# at90usb.net
KiCad netlist of a schematic drawn in EAGLE
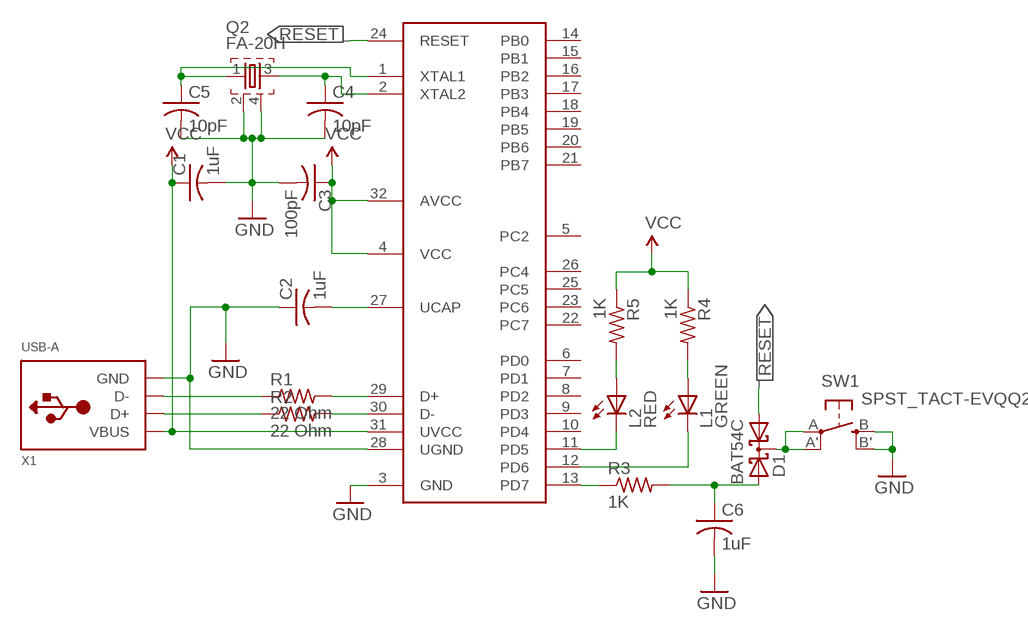
[diagram p0: schematic, sheet 1]

(export (version "E")
  (design (tool "Eeschema 10.0.6"))
  (components
    (comp (ref "C1")
      (value "1uF")
      (footprint "eagle-import:C0805K")
      (fields (field (name "MPN") "06033D105MAT2A"))
      (libsource (lib "eagle-import") (part "C-USC0805K"))
    )
    (comp (ref "C2")
      (value "1uF")
      (footprint "eagle-import:C0805K")
      (fields (field (name "MPN") "06033D105MAT2A"))
      (libsource (lib "eagle-import") (part "C-USC0805K"))
    )
    (comp (ref "C3")
      (value "100pF")
      (footprint "eagle-import:C0805K")
      (fields (field (name "MPN") "0603YC104K4Z2A"))
      (libsource (lib "eagle-import") (part "C-USC0805K"))
    )
    (comp (ref "C4")
      (value "10pF")
      (footprint "eagle-import:C0805")
      (libsource (lib "eagle-import") (part "C-USC0805"))
    )
    (comp (ref "C5")
      (value "10pF")
      (footprint "eagle-import:C0805")
      (libsource (lib "eagle-import") (part "C-USC0805"))
    )
    (comp (ref "C6")
      (value "1uF")
      (footprint "eagle-import:C0805K")
      (fields (field (name "MPN") "06033D105MAT2A"))
      (libsource (lib "eagle-import") (part "C-USC0805K"))
    )
    (comp (ref "D1")
      (value "BAT54C")
      (footprint "eagle-import:SOT23")
      (libsource (lib "eagle-import") (part "BAT54C"))
    )
    (comp (ref "L1")
      (value "GREEN")
      (footprint "eagle-import:CHIPLED_1206")
      (libsource (lib "eagle-import") (part "LEDCHIPLED_1206"))
    )
    (comp (ref "L2")
      (value "RED")
      (footprint "eagle-import:CHIPLED_1206")
      (libsource (lib "eagle-import") (part "LEDCHIPLED_1206"))
    )
    (comp (ref "Q2")
      (value "FA-20H")
      (footprint "eagle-import:FA-20H")
      (libsource (lib "eagle-import") (part "FA-20H"))
    )
    (comp (ref "R1")
      (value "22 Ohm")
      (footprint "eagle-import:M0805")
      (libsource (lib "eagle-import") (part "R-US_M0805"))
    )
    (comp (ref "R2")
      (value "22 Ohm")
      (footprint "eagle-import:M0805")
      (libsource (lib "eagle-import") (part "R-US_M0805"))
    )
    (comp (ref "R3")
      (value "1K")
      (footprint "eagle-import:M0805")
      (libsource (lib "eagle-import") (part "R-US_M0805"))
    )
    (comp (ref "R4")
      (value "1K")
      (footprint "eagle-import:M0805")
      (libsource (lib "eagle-import") (part "R-US_M0805"))
    )
    (comp (ref "R5")
      (value "1K")
      (footprint "eagle-import:M0805")
      (libsource (lib "eagle-import") (part "R-US_M0805"))
    )
    (comp (ref "SW1")
      (value "SPST_TACT-EVQQ2")
      (footprint "eagle-import:EVQ-Q2")
      (libsource (lib "eagle-import") (part "SPST_TACT-EVQQ2"))
    )
    (comp (ref "U1")
      (value "AT90USB162")
      (footprint "eagle-import:VQFP32")
      (libsource (lib "eagle-import") (part "AT90USB162"))
    )
    (comp (ref "X1")
      (value "USB-A")
      (footprint "eagle-import:MOLEX_480371000")
      (libsource (lib "eagle-import") (part "USB-A"))
    )
  )
  (nets
    (net (code "1") (name "/RESET") (class "Default")
      (node (ref "D1") (pin "1") (pinfunction "A1_1") (pintype "passive"))
      (node (ref "U1") (pin "24") (pinfunction "RESET_24") (pintype "bidirectional"))
    )
    (net (code "2") (name "GND") (class "Default")
      (node (ref "C1") (pin "2") (pinfunction "2_2") (pintype "passive"))
      (node (ref "C2") (pin "1") (pinfunction "1_1") (pintype "passive"))
      (node (ref "C3") (pin "2") (pinfunction "2_2") (pintype "passive"))
      (node (ref "C4") (pin "2") (pinfunction "2_2") (pintype "passive"))
      (node (ref "C5") (pin "2") (pinfunction "2_2") (pintype "passive"))
      (node (ref "C6") (pin "2") (pinfunction "2_2") (pintype "passive"))
      (node (ref "Q2") (pin "2") (pinfunction "2_2") (pintype "passive"))
      (node (ref "Q2") (pin "4") (pinfunction "4_4") (pintype "passive"))
      (node (ref "SW1") (pin "B") (pinfunction "S_B") (pintype "passive"))
      (node (ref "SW1") (pin "B'") (pinfunction "S1_B'") (pintype "passive"))
      (node (ref "U1") (pin "28") (pinfunction "UGND_28") (pintype "bidirectional"))
      (node (ref "U1") (pin "3") (pinfunction "GND_3") (pintype "power_in"))
      (node (ref "X1") (pin "4") (pinfunction "GND_4") (pintype "power_in"))
    )
    (net (code "3") (name "Net-(D1-A2)") (class "Default")
      (node (ref "C6") (pin "1") (pinfunction "1_1") (pintype "passive"))
      (node (ref "D1") (pin "2") (pinfunction "A2_2") (pintype "passive"))
      (node (ref "R3") (pin "2") (pinfunction "2_2") (pintype "passive"))
    )
    (net (code "4") (name "Net-(D1-CC)") (class "Default")
      (node (ref "D1") (pin "3") (pinfunction "CC_3") (pintype "passive"))
      (node (ref "SW1") (pin "A") (pinfunction "P_A") (pintype "passive"))
      (node (ref "SW1") (pin "A'") (pinfunction "P1_A'") (pintype "passive"))
    )
    (net (code "5") (name "Net-(L1-PadA)") (class "Default")
      (node (ref "L1") (pin "A") (pinfunction "A_A") (pintype "passive"))
      (node (ref "R4") (pin "2") (pinfunction "2_2") (pintype "passive"))
    )
    (net (code "6") (name "Net-(L2-PadA)") (class "Default")
      (node (ref "L2") (pin "A") (pinfunction "A_A") (pintype "passive"))
      (node (ref "R5") (pin "2") (pinfunction "2_2") (pintype "passive"))
    )
    (net (code "7") (name "Net-(U1-D+)") (class "Default")
      (node (ref "R1") (pin "2") (pinfunction "2_2") (pintype "passive"))
      (node (ref "U1") (pin "29") (pinfunction "D+_29") (pintype "bidirectional"))
    )
    (net (code "8") (name "Net-(U1-D-)") (class "Default")
      (node (ref "R2") (pin "2") (pinfunction "2_2") (pintype "passive"))
      (node (ref "U1") (pin "30") (pinfunction "D-_30") (pintype "bidirectional"))
    )
    (net (code "9") (name "Net-(U1-PD5)") (class "Default")
      (node (ref "L2") (pin "C") (pinfunction "C_C") (pintype "passive"))
      (node (ref "U1") (pin "11") (pinfunction "PD5_11") (pintype "bidirectional"))
    )
    (net (code "10") (name "Net-(U1-PD6)") (class "Default")
      (node (ref "L1") (pin "C") (pinfunction "C_C") (pintype "passive"))
      (node (ref "U1") (pin "12") (pinfunction "PD6_12") (pintype "bidirectional"))
    )
    (net (code "11") (name "Net-(U1-PD7)") (class "Default")
      (node (ref "R3") (pin "1") (pinfunction "1_1") (pintype "passive"))
      (node (ref "U1") (pin "13") (pinfunction "PD7_13") (pintype "bidirectional"))
    )
    (net (code "12") (name "Net-(U1-UCAP)") (class "Default")
      (node (ref "C2") (pin "2") (pinfunction "2_2") (pintype "passive"))
      (node (ref "U1") (pin "27") (pinfunction "UCAP_27") (pintype "bidirectional"))
    )
    (net (code "13") (name "Net-(U1-XTAL1)") (class "Default")
      (node (ref "C5") (pin "1") (pinfunction "1_1") (pintype "passive"))
      (node (ref "Q2") (pin "1") (pinfunction "1_1") (pintype "passive"))
      (node (ref "U1") (pin "1") (pinfunction "XTAL1_1") (pintype "bidirectional"))
    )
    (net (code "14") (name "Net-(U1-XTAL2)") (class "Default")
      (node (ref "C4") (pin "1") (pinfunction "1_1") (pintype "passive"))
      (node (ref "Q2") (pin "3") (pinfunction "3_3") (pintype "passive"))
      (node (ref "U1") (pin "2") (pinfunction "XTAL2_2") (pintype "bidirectional"))
    )
    (net (code "15") (name "Net-(X1-D+)") (class "Default")
      (node (ref "R2") (pin "1") (pinfunction "1_1") (pintype "passive"))
      (node (ref "X1") (pin "3") (pinfunction "D+_3") (pintype "bidirectional"))
    )
    (net (code "16") (name "Net-(X1-D-)") (class "Default")
      (node (ref "R1") (pin "1") (pinfunction "1_1") (pintype "passive"))
      (node (ref "X1") (pin "2") (pinfunction "D-_2") (pintype "bidirectional"))
    )
    (net (code "17") (name "VCC") (class "Default")
      (node (ref "C1") (pin "1") (pinfunction "1_1") (pintype "passive"))
      (node (ref "C3") (pin "1") (pinfunction "1_1") (pintype "passive"))
      (node (ref "R4") (pin "1") (pinfunction "1_1") (pintype "passive"))
      (node (ref "R5") (pin "1") (pinfunction "1_1") (pintype "passive"))
      (node (ref "U1") (pin "31") (pinfunction "UVCC_31") (pintype "bidirectional"))
      (node (ref "U1") (pin "32") (pinfunction "AVCC_32") (pintype "bidirectional"))
      (node (ref "U1") (pin "4") (pinfunction "VCC_4") (pintype "power_in"))
      (node (ref "X1") (pin "1") (pinfunction "VBUS_1") (pintype "power_in"))
    )
    (net (code "18") (name "unconnected-(U1-PB0-Pad14)") (class "Default")
      (node (ref "U1") (pin "14") (pinfunction "PB0_14") (pintype "bidirectional"))
    )
    (net (code "19") (name "unconnected-(U1-PB1-Pad15)") (class "Default")
      (node (ref "U1") (pin "15") (pinfunction "PB1_15") (pintype "bidirectional"))
    )
    (net (code "20") (name "unconnected-(U1-PB2-Pad16)") (class "Default")
      (node (ref "U1") (pin "16") (pinfunction "PB2_16") (pintype "bidirectional"))
    )
    (net (code "21") (name "unconnected-(U1-PB3-Pad17)") (class "Default")
      (node (ref "U1") (pin "17") (pinfunction "PB3_17") (pintype "bidirectional"))
    )
    (net (code "22") (name "unconnected-(U1-PB4-Pad18)") (class "Default")
      (node (ref "U1") (pin "18") (pinfunction "PB4_18") (pintype "bidirectional"))
    )
    (net (code "23") (name "unconnected-(U1-PB5-Pad19)") (class "Default")
      (node (ref "U1") (pin "19") (pinfunction "PB5_19") (pintype "bidirectional"))
    )
    (net (code "24") (name "unconnected-(U1-PB6-Pad20)") (class "Default")
      (node (ref "U1") (pin "20") (pinfunction "PB6_20") (pintype "bidirectional"))
    )
    (net (code "25") (name "unconnected-(U1-PB7-Pad21)") (class "Default")
      (node (ref "U1") (pin "21") (pinfunction "PB7_21") (pintype "bidirectional"))
    )
    (net (code "26") (name "unconnected-(U1-PC2-Pad5)") (class "Default")
      (node (ref "U1") (pin "5") (pinfunction "PC2_5") (pintype "bidirectional"))
    )
    (net (code "27") (name "unconnected-(U1-PC4-Pad26)") (class "Default")
      (node (ref "U1") (pin "26") (pinfunction "PC4_26") (pintype "bidirectional"))
    )
    (net (code "28") (name "unconnected-(U1-PC5-Pad25)") (class "Default")
      (node (ref "U1") (pin "25") (pinfunction "PC5_25") (pintype "bidirectional"))
    )
    (net (code "29") (name "unconnected-(U1-PC6-Pad23)") (class "Default")
      (node (ref "U1") (pin "23") (pinfunction "PC6_23") (pintype "bidirectional"))
    )
    (net (code "30") (name "unconnected-(U1-PC7-Pad22)") (class "Default")
      (node (ref "U1") (pin "22") (pinfunction "PC7_22") (pintype "bidirectional"))
    )
    (net (code "31") (name "unconnected-(U1-PD0-Pad6)") (class "Default")
      (node (ref "U1") (pin "6") (pinfunction "PD0_6") (pintype "bidirectional"))
    )
    (net (code "32") (name "unconnected-(U1-PD1-Pad7)") (class "Default")
      (node (ref "U1") (pin "7") (pinfunction "PD1_7") (pintype "bidirectional"))
    )
    (net (code "33") (name "unconnected-(U1-PD2-Pad8)") (class "Default")
      (node (ref "U1") (pin "8") (pinfunction "PD2_8") (pintype "bidirectional"))
    )
    (net (code "34") (name "unconnected-(U1-PD3-Pad9)") (class "Default")
      (node (ref "U1") (pin "9") (pinfunction "PD3_9") (pintype "bidirectional"))
    )
    (net (code "35") (name "unconnected-(U1-PD4-Pad10)") (class "Default")
      (node (ref "U1") (pin "10") (pinfunction "PD4_10") (pintype "bidirectional"))
    )
  )
)
